# TFT_Display_Interface.net
KiCad netlist of a schematic drawn in Altium Designer
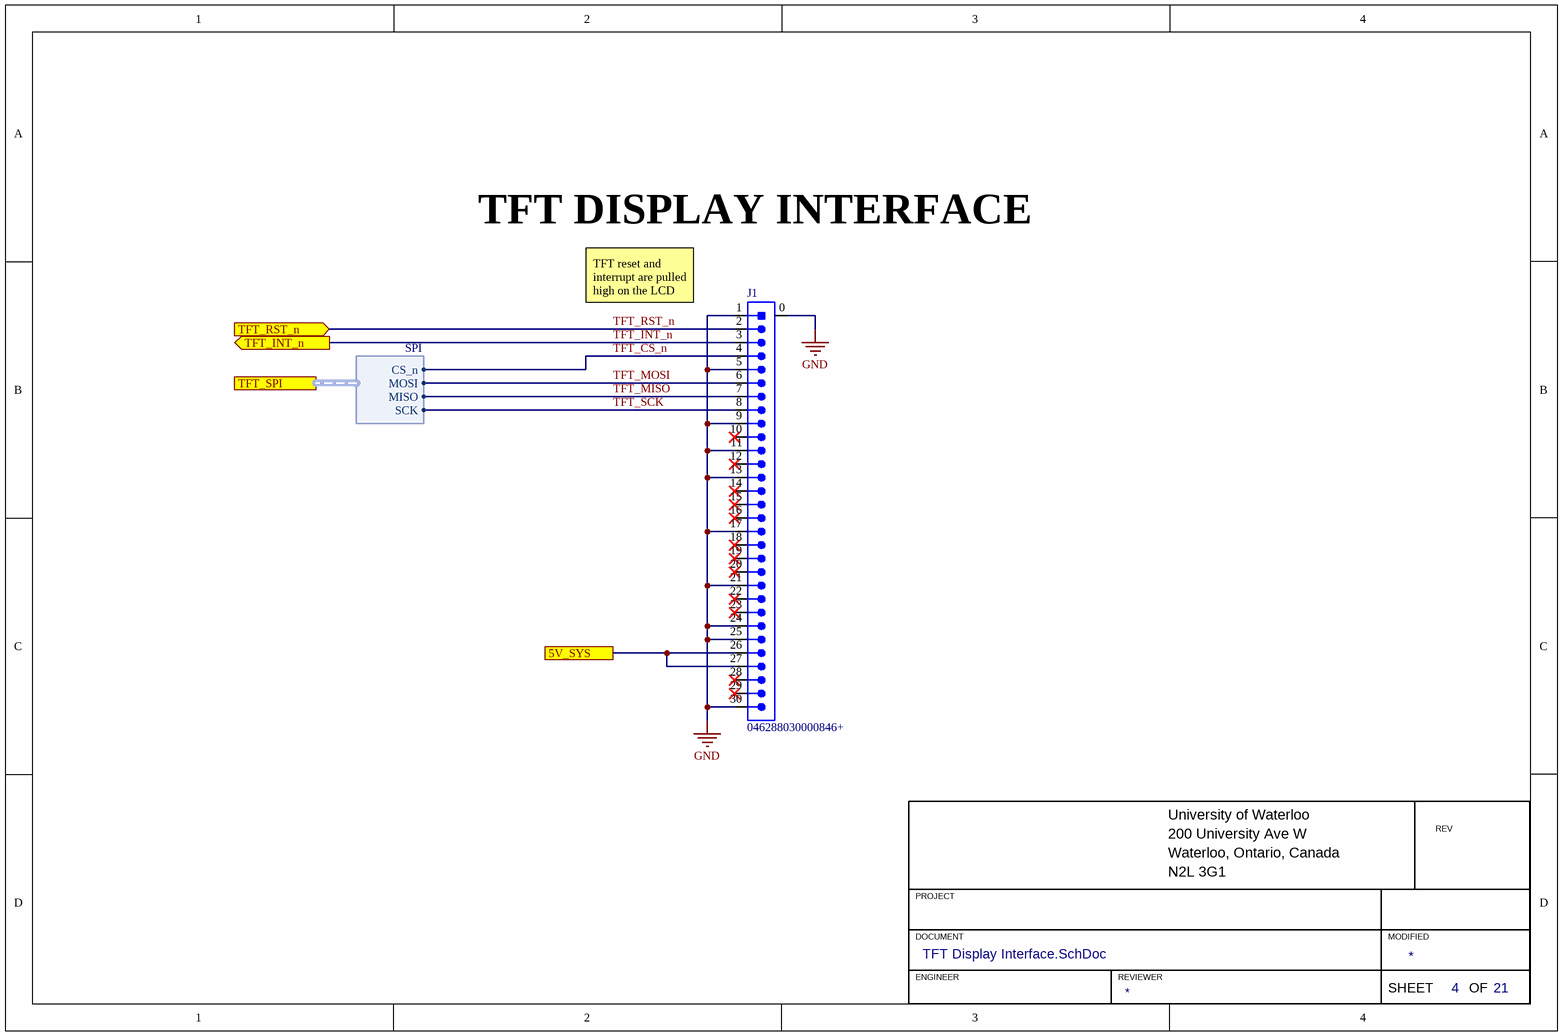
[diagram p0: TFT Display Interface.SchDoc]

(export (version "E")
  (design (tool "Eeschema 10.0.6"))
  (components
    (comp (ref "J1")
      (value "CON_MOLEX-FFC_30P_RA")
      (footprint "MOLEX_FFC_30P_RA")
      (description "CONN FFC BOTTOM 30POS 0.5MM R/A")
      (fields (field (name "MANUFACTURER PART NUMBER 1") "046288030000846+"))
      (libsource (lib "Personal_Schematic_Library_2022") (part "CON_MOLEX-FFC_30P_RA"))
    )
  )
  (nets
    (net (code "2") (name "/5V_SYS") (class "Default")
      (node (ref "J1") (pin "26") (pinfunction "26_26") (pintype "passive"))
      (node (ref "J1") (pin "27") (pinfunction "27_27") (pintype "passive"))
    )
    (net (code "3") (name "/TFT_CS_n") (class "Default")
      (node (ref "J1") (pin "4") (pinfunction "4_4") (pintype "passive"))
    )
    (net (code "4") (name "/TFT_INT_n") (class "Default")
      (node (ref "J1") (pin "3") (pinfunction "3_3") (pintype "passive"))
    )
    (net (code "5") (name "/TFT_MISO") (class "Default")
      (node (ref "J1") (pin "7") (pinfunction "6_7") (pintype "passive"))
    )
    (net (code "6") (name "/TFT_MOSI") (class "Default")
      (node (ref "J1") (pin "6") (pinfunction "6_6") (pintype "passive"))
    )
    (net (code "7") (name "/TFT_RST_n") (class "Default")
      (node (ref "J1") (pin "2") (pinfunction "2_2") (pintype "passive"))
    )
    (net (code "8") (name "/TFT_SCK") (class "Default")
      (node (ref "J1") (pin "8") (pinfunction "6_8") (pintype "passive"))
    )
    (net (code "10") (name "GND") (class "Default")
      (node (ref "J1") (pin "0") (pinfunction "0_0") (pintype "passive"))
      (node (ref "J1") (pin "1") (pinfunction "1_1") (pintype "passive"))
      (node (ref "J1") (pin "11") (pinfunction "11_11") (pintype "passive"))
      (node (ref "J1") (pin "13") (pinfunction "13_13") (pintype "passive"))
      (node (ref "J1") (pin "17") (pinfunction "17_17") (pintype "passive"))
      (node (ref "J1") (pin "21") (pinfunction "21_21") (pintype "passive"))
      (node (ref "J1") (pin "24") (pinfunction "24_24") (pintype "passive"))
      (node (ref "J1") (pin "25") (pinfunction "25_25") (pintype "passive"))
      (node (ref "J1") (pin "30") (pinfunction "30_30") (pintype "passive"))
      (node (ref "J1") (pin "5") (pinfunction "5_5") (pintype "passive"))
      (node (ref "J1") (pin "9") (pinfunction "9_9") (pintype "passive"))
    )
    (net (code "11") (name "unconnected-(J1-Pad10)") (class "Default")
      (node (ref "J1") (pin "10") (pinfunction "10_10") (pintype "passive+no_connect"))
    )
    (net (code "12") (name "unconnected-(J1-Pad12)") (class "Default")
      (node (ref "J1") (pin "12") (pinfunction "12_12") (pintype "passive+no_connect"))
    )
    (net (code "13") (name "unconnected-(J1-Pad14)") (class "Default")
      (node (ref "J1") (pin "14") (pinfunction "14_14") (pintype "passive+no_connect"))
    )
    (net (code "14") (name "unconnected-(J1-Pad15)") (class "Default")
      (node (ref "J1") (pin "15") (pinfunction "15_15") (pintype "passive+no_connect"))
    )
    (net (code "15") (name "unconnected-(J1-Pad16)") (class "Default")
      (node (ref "J1") (pin "16") (pinfunction "16_16") (pintype "passive+no_connect"))
    )
    (net (code "16") (name "unconnected-(J1-Pad18)") (class "Default")
      (node (ref "J1") (pin "18") (pinfunction "18_18") (pintype "passive+no_connect"))
    )
    (net (code "17") (name "unconnected-(J1-Pad19)") (class "Default")
      (node (ref "J1") (pin "19") (pinfunction "19_19") (pintype "passive+no_connect"))
    )
    (net (code "18") (name "unconnected-(J1-Pad20)") (class "Default")
      (node (ref "J1") (pin "20") (pinfunction "20_20") (pintype "passive+no_connect"))
    )
    (net (code "19") (name "unconnected-(J1-Pad22)") (class "Default")
      (node (ref "J1") (pin "22") (pinfunction "22_22") (pintype "passive+no_connect"))
    )
    (net (code "20") (name "unconnected-(J1-Pad23)") (class "Default")
      (node (ref "J1") (pin "23") (pinfunction "23_23") (pintype "passive+no_connect"))
    )
    (net (code "21") (name "unconnected-(J1-Pad28)") (class "Default")
      (node (ref "J1") (pin "28") (pinfunction "28_28") (pintype "passive+no_connect"))
    )
    (net (code "22") (name "unconnected-(J1-Pad29)") (class "Default")
      (node (ref "J1") (pin "29") (pinfunction "29_29") (pintype "passive+no_connect"))
    )
  )
)
